# vias.net
KiCad netlist of a schematic drawn in Altium Designer
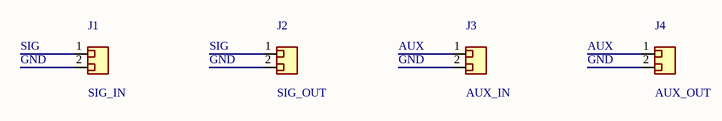
[diagram p0: vias.SchDoc]

(export (version "E")
  (design (tool "Eeschema 10.0.6"))
  (components
    (comp (ref "J1")
      (value "SIG_IN")
      (footprint "vias:Header_1x2_P2.54")
      (libsource (lib "vias") (part "Connector_2"))
    )
    (comp (ref "J2")
      (value "SIG_OUT")
      (footprint "vias:Header_1x2_P2.54")
      (libsource (lib "vias") (part "Connector_2"))
    )
    (comp (ref "J3")
      (value "AUX_IN")
      (footprint "vias:Header_1x2_P2.54")
      (libsource (lib "vias") (part "Connector_2"))
    )
    (comp (ref "J4")
      (value "AUX_OUT")
      (footprint "vias:Header_1x2_P2.54")
      (libsource (lib "vias") (part "Connector_2"))
    )
  )
  (nets
    (net (code "1") (name "/AUX") (class "Default")
      (node (ref "J3") (pin "1") (pinfunction "Passive_1") (pintype "passive"))
      (node (ref "J4") (pin "1") (pinfunction "Passive_1") (pintype "passive"))
    )
    (net (code "2") (name "/GND") (class "Default")
      (node (ref "J1") (pin "2") (pinfunction "Passive_2") (pintype "passive"))
      (node (ref "J2") (pin "2") (pinfunction "Passive_2") (pintype "passive"))
      (node (ref "J3") (pin "2") (pinfunction "Passive_2") (pintype "passive"))
      (node (ref "J4") (pin "2") (pinfunction "Passive_2") (pintype "passive"))
    )
    (net (code "3") (name "/SIG") (class "Default")
      (node (ref "J1") (pin "1") (pinfunction "Passive_1") (pintype "passive"))
      (node (ref "J2") (pin "1") (pinfunction "Passive_1") (pintype "passive"))
    )
  )
)
